# 02-WIFT_BT.net
KiCad netlist of a schematic drawn in Altium Designer
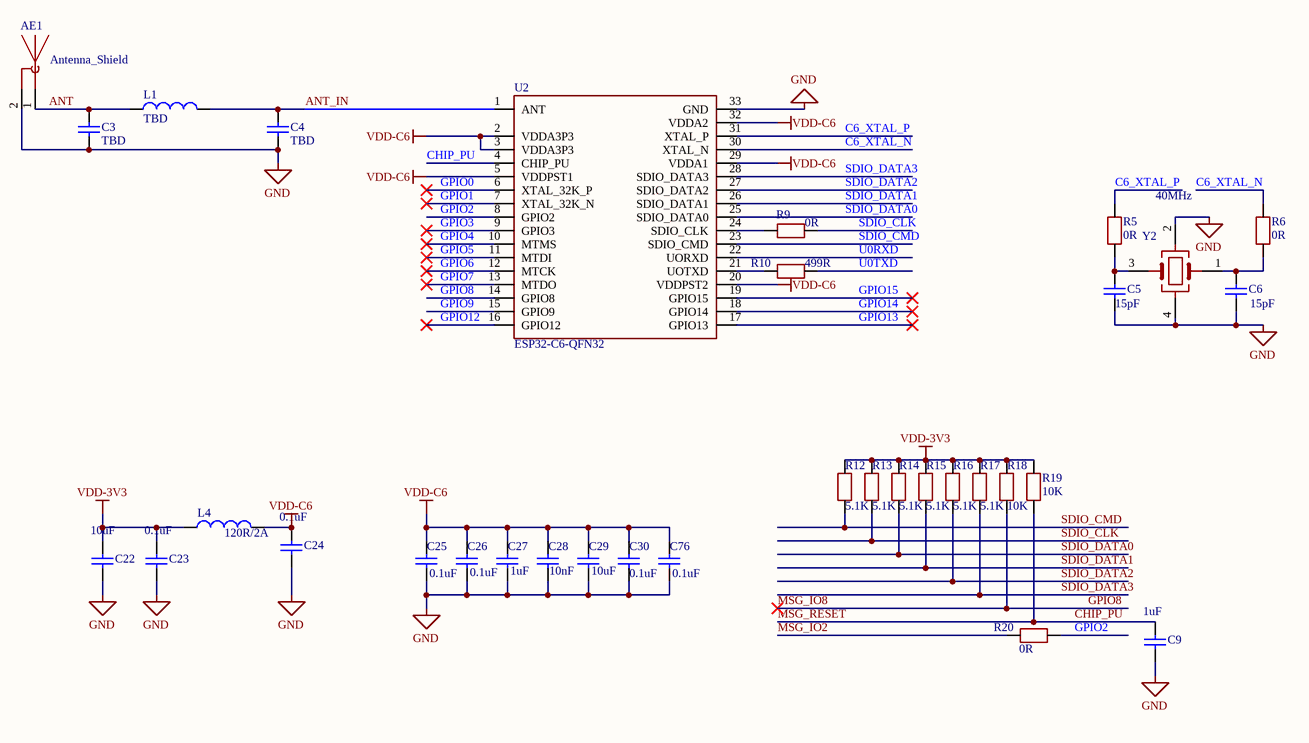
[diagram p0: 02-WIFT+BT.SchDoc]

(export (version "E")
  (design (tool "Eeschema 10.0.6"))
  (components
    (comp (ref "AE1")
      (value "Antenna_Shield")
      (footprint "ANT")
      (libsource (lib "222222") (part "Component_1"))
    )
    (comp (ref "C3")
      (value "TBD")
      (footprint "C0402")
      (description "Capacitor")
      (libsource (lib "Simulation Generic Components") (part "Capacitor"))
    )
    (comp (ref "C4")
      (value "TBD")
      (footprint "C0402")
      (description "Capacitor")
      (libsource (lib "Simulation Generic Components") (part "Capacitor"))
    )
    (comp (ref "C5")
      (value "15pF")
      (footprint "C0402")
      (description "Capacitor")
      (libsource (lib "Simulation Generic Components") (part "Capacitor"))
    )
    (comp (ref "C6")
      (value "15pF")
      (footprint "C0402")
      (description "Capacitor")
      (libsource (lib "Simulation Generic Components") (part "Capacitor"))
    )
    (comp (ref "C9")
      (value "1uF")
      (footprint "C0402")
      (description "Capacitor")
      (libsource (lib "Simulation Generic Components") (part "Capacitor"))
    )
    (comp (ref "C22")
      (value "10uF")
      (footprint "C0805")
      (description "Capacitor")
      (libsource (lib "Simulation Generic Components") (part "Capacitor"))
    )
    (comp (ref "C23")
      (value "0.1uF")
      (footprint "C0402")
      (description "Capacitor")
      (libsource (lib "Simulation Generic Components") (part "Capacitor"))
    )
    (comp (ref "C24")
      (value "0.1uF")
      (footprint "C0402")
      (description "Capacitor")
      (libsource (lib "Simulation Generic Components") (part "Capacitor"))
    )
    (comp (ref "C25")
      (value "0.1uF")
      (footprint "C0402")
      (description "Capacitor")
      (libsource (lib "Simulation Generic Components") (part "Capacitor"))
    )
    (comp (ref "C26")
      (value "0.1uF")
      (footprint "C0402")
      (description "Capacitor")
      (libsource (lib "Simulation Generic Components") (part "Capacitor"))
    )
    (comp (ref "C27")
      (value "1uF")
      (footprint "C0402")
      (description "Capacitor")
      (libsource (lib "Simulation Generic Components") (part "Capacitor"))
    )
    (comp (ref "C28")
      (value "10nF")
      (footprint "C0402")
      (description "Capacitor")
      (libsource (lib "Simulation Generic Components") (part "Capacitor"))
    )
    (comp (ref "C29")
      (value "10uF")
      (footprint "C0805")
      (description "Capacitor")
      (libsource (lib "Simulation Generic Components") (part "Capacitor"))
    )
    (comp (ref "C30")
      (value "0.1uF")
      (footprint "C0402")
      (description "Capacitor")
      (libsource (lib "Simulation Generic Components") (part "Capacitor"))
    )
    (comp (ref "C76")
      (value "0.1uF")
      (footprint "C0402")
      (description "Capacitor")
      (libsource (lib "Simulation Generic Components") (part "Capacitor"))
    )
    (comp (ref "L1")
      (value "TBD")
      (footprint "L0603")
      (description "Inductor")
      (libsource (lib "Simulation Generic Components") (part "Inductor"))
    )
    (comp (ref "L4")
      (value "120R/2A")
      (footprint "L0603")
      (description "Inductor")
      (libsource (lib "Simulation Generic Components") (part "Inductor"))
    )
    (comp (ref "R5") (value "0R") (footprint "R0402") (libsource (lib "PCB_Project") (part "R")))
    (comp (ref "R6") (value "0R") (footprint "R0402") (libsource (lib "PCB_Project") (part "R")))
    (comp (ref "R9") (value "0R") (footprint "R0402") (libsource (lib "PCB_Project") (part "R")))
    (comp (ref "R10") (value "499R") (footprint "R0402") (libsource (lib "PCB_Project") (part "R")))
    (comp (ref "R12") (value "5.1K") (footprint "R0402") (libsource (lib "PCB_Project") (part "R")))
    (comp (ref "R13") (value "5.1K") (footprint "R0402") (libsource (lib "PCB_Project") (part "R")))
    (comp (ref "R14") (value "5.1K") (footprint "R0402") (libsource (lib "PCB_Project") (part "R")))
    (comp (ref "R15") (value "5.1K") (footprint "R0402") (libsource (lib "PCB_Project") (part "R")))
    (comp (ref "R16") (value "5.1K") (footprint "R0402") (libsource (lib "PCB_Project") (part "R")))
    (comp (ref "R17") (value "5.1K") (footprint "R0402") (libsource (lib "PCB_Project") (part "R")))
    (comp (ref "R18") (value "10K") (footprint "R0402") (libsource (lib "PCB_Project") (part "R")))
    (comp (ref "R19") (value "10K") (footprint "R0402") (libsource (lib "PCB_Project") (part "R")))
    (comp (ref "R20") (value "0R") (footprint "R0402") (libsource (lib "PCB_Project") (part "R")))
    (comp (ref "U2")
      (value "ESP32-C6-QFN32")
      (footprint "QFN-32_L5.0-W5.0-P0.50-TL-EP3.7")
      (libsource (lib "222222") (part "ESP32-C6-QFN32"))
    )
    (comp (ref "Y2")
      (value "40MHz")
      (footprint "OSC-SMD_4P-L3.2-W2.5-BL_SIT8008BI")
      (libsource (lib "222222") (part "Component_3"))
    )
  )
  (nets
    (net (code "1") (name "/ANT") (class "Default")
      (node (ref "AE1") (pin "1") (pinfunction "1_1") (pintype "passive"))
      (node (ref "C3") (pin "2") (pinfunction "2_2") (pintype "passive"))
      (node (ref "L1") (pin "1") (pinfunction "1_1") (pintype "passive"))
    )
    (net (code "2") (name "/ANT_IN") (class "Default")
      (node (ref "C4") (pin "2") (pinfunction "2_2") (pintype "passive"))
      (node (ref "L1") (pin "2") (pinfunction "2_2") (pintype "passive"))
      (node (ref "U2") (pin "1") (pinfunction "ANT_1") (pintype "passive"))
    )
    (net (code "3") (name "/C6_XTAL_N") (class "Default")
      (node (ref "R6") (pin "2") (pinfunction "2_2") (pintype "passive"))
      (node (ref "U2") (pin "30") (pinfunction "XTAL_N_30") (pintype "passive"))
    )
    (net (code "4") (name "/C6_XTAL_P") (class "Default")
      (node (ref "R5") (pin "2") (pinfunction "2_2") (pintype "passive"))
      (node (ref "U2") (pin "31") (pinfunction "XTAL_P_31") (pintype "passive"))
    )
    (net (code "5") (name "/CHIP_PU") (class "Default")
      (node (ref "C9") (pin "2") (pinfunction "2_2") (pintype "passive"))
      (node (ref "R19") (pin "2") (pinfunction "2_2") (pintype "passive"))
      (node (ref "U2") (pin "4") (pinfunction "CHIP_PU_4") (pintype "passive"))
    )
    (net (code "6") (name "/GPIO0") (class "Default")
      (node (ref "U2") (pin "6") (pinfunction "XTAL_32K_P_6") (pintype "passive+no_connect"))
    )
    (net (code "7") (name "/GPIO1") (class "Default")
      (node (ref "U2") (pin "7") (pinfunction "XTAL_32K_N_7") (pintype "passive+no_connect"))
    )
    (net (code "8") (name "/GPIO2") (class "Default")
      (node (ref "R20") (pin "2") (pinfunction "2_2") (pintype "passive"))
      (node (ref "U2") (pin "8") (pinfunction "GPIO2_8") (pintype "passive"))
    )
    (net (code "9") (name "/GPIO3") (class "Default")
      (node (ref "U2") (pin "9") (pinfunction "GPIO3_9") (pintype "passive+no_connect"))
    )
    (net (code "10") (name "/GPIO4") (class "Default")
      (node (ref "U2") (pin "10") (pinfunction "MTMS_10") (pintype "passive+no_connect"))
    )
    (net (code "11") (name "/GPIO5") (class "Default")
      (node (ref "U2") (pin "11") (pinfunction "MTDI_11") (pintype "passive+no_connect"))
    )
    (net (code "12") (name "/GPIO6") (class "Default")
      (node (ref "U2") (pin "12") (pinfunction "MTCK_12") (pintype "passive+no_connect"))
    )
    (net (code "13") (name "/GPIO7") (class "Default")
      (node (ref "U2") (pin "13") (pinfunction "MTDO_13") (pintype "passive+no_connect"))
    )
    (net (code "14") (name "/GPIO8") (class "Default")
      (node (ref "R18") (pin "2") (pinfunction "2_2") (pintype "passive"))
      (node (ref "U2") (pin "14") (pinfunction "GPIO8_14") (pintype "passive"))
    )
    (net (code "15") (name "/GPIO9") (class "Default")
      (node (ref "U2") (pin "15") (pinfunction "GPIO9_15") (pintype "passive"))
    )
    (net (code "16") (name "/GPIO12") (class "Default")
      (node (ref "U2") (pin "16") (pinfunction "GPIO12_16") (pintype "passive+no_connect"))
    )
    (net (code "17") (name "/GPIO13") (class "Default")
      (node (ref "U2") (pin "17") (pinfunction "GPIO13_17") (pintype "passive+no_connect"))
    )
    (net (code "18") (name "/GPIO14") (class "Default")
      (node (ref "U2") (pin "18") (pinfunction "GPIO14_18") (pintype "passive+no_connect"))
    )
    (net (code "19") (name "/GPIO15") (class "Default")
      (node (ref "U2") (pin "19") (pinfunction "GPIO15_19") (pintype "passive+no_connect"))
    )
    (net (code "20") (name "/MSG_IO2") (class "Default")
      (node (ref "R20") (pin "1") (pinfunction "1_1") (pintype "passive"))
    )
    (net (code "21") (name "/SDIO_CLK") (class "Default")
      (node (ref "R13") (pin "2") (pinfunction "2_2") (pintype "passive"))
      (node (ref "R9") (pin "2") (pinfunction "2_2") (pintype "passive"))
    )
    (net (code "22") (name "/SDIO_CMD") (class "Default")
      (node (ref "R12") (pin "2") (pinfunction "2_2") (pintype "passive"))
      (node (ref "U2") (pin "23") (pinfunction "SDIO_CMD_23") (pintype "passive"))
    )
    (net (code "23") (name "/SDIO_DATA0") (class "Default")
      (node (ref "R14") (pin "2") (pinfunction "2_2") (pintype "passive"))
      (node (ref "U2") (pin "25") (pinfunction "SDIO_DATA0_25") (pintype "passive"))
    )
    (net (code "24") (name "/SDIO_DATA1") (class "Default")
      (node (ref "R15") (pin "2") (pinfunction "2_2") (pintype "passive"))
      (node (ref "U2") (pin "26") (pinfunction "SDIO_DATA1_26") (pintype "passive"))
    )
    (net (code "25") (name "/SDIO_DATA2") (class "Default")
      (node (ref "R16") (pin "2") (pinfunction "2_2") (pintype "passive"))
      (node (ref "U2") (pin "27") (pinfunction "SDIO_DATA2_27") (pintype "passive"))
    )
    (net (code "26") (name "/SDIO_DATA3") (class "Default")
      (node (ref "R17") (pin "2") (pinfunction "2_2") (pintype "passive"))
      (node (ref "U2") (pin "28") (pinfunction "SDIO_DATA3_28") (pintype "passive"))
    )
    (net (code "27") (name "/U0RXD") (class "Default")
      (node (ref "U2") (pin "22") (pinfunction "UORXD_22") (pintype "passive"))
    )
    (net (code "28") (name "/U0TXD") (class "Default")
      (node (ref "R10") (pin "2") (pinfunction "2_2") (pintype "passive"))
    )
    (net (code "29") (name "GND") (class "Default")
      (node (ref "AE1") (pin "2") (pinfunction "2_2") (pintype "passive"))
      (node (ref "C22") (pin "1") (pinfunction "1_1") (pintype "passive"))
      (node (ref "C23") (pin "1") (pinfunction "1_1") (pintype "passive"))
      (node (ref "C24") (pin "2") (pinfunction "2_2") (pintype "passive"))
      (node (ref "C25") (pin "2") (pinfunction "2_2") (pintype "passive"))
      (node (ref "C26") (pin "2") (pinfunction "2_2") (pintype "passive"))
      (node (ref "C27") (pin "2") (pinfunction "2_2") (pintype "passive"))
      (node (ref "C28") (pin "2") (pinfunction "2_2") (pintype "passive"))
      (node (ref "C29") (pin "2") (pinfunction "2_2") (pintype "passive"))
      (node (ref "C3") (pin "1") (pinfunction "1_1") (pintype "passive"))
      (node (ref "C30") (pin "1") (pinfunction "1_1") (pintype "passive"))
      (node (ref "C4") (pin "1") (pinfunction "1_1") (pintype "passive"))
      (node (ref "C5") (pin "2") (pinfunction "2_2") (pintype "passive"))
      (node (ref "C6") (pin "2") (pinfunction "2_2") (pintype "passive"))
      (node (ref "C76") (pin "2") (pinfunction "2_2") (pintype "passive"))
      (node (ref "C9") (pin "1") (pinfunction "1_1") (pintype "passive"))
      (node (ref "U2") (pin "33") (pinfunction "GND_33") (pintype "passive"))
      (node (ref "Y2") (pin "2") (pinfunction "2_2") (pintype "passive"))
      (node (ref "Y2") (pin "4") (pinfunction "4_4") (pintype "passive"))
    )
    (net (code "30") (name "Net-(C5-Pad1)") (class "Default")
      (node (ref "C5") (pin "1") (pinfunction "1_1") (pintype "passive"))
      (node (ref "R5") (pin "1") (pinfunction "1_1") (pintype "passive"))
      (node (ref "Y2") (pin "3") (pinfunction "3_3") (pintype "passive"))
    )
    (net (code "31") (name "Net-(C6-Pad1)") (class "Default")
      (node (ref "C6") (pin "1") (pinfunction "1_1") (pintype "passive"))
      (node (ref "R6") (pin "1") (pinfunction "1_1") (pintype "passive"))
      (node (ref "Y2") (pin "1") (pinfunction "1_1") (pintype "passive"))
    )
    (net (code "32") (name "Net-(U2-SDIO_CLK)") (class "Default")
      (node (ref "R9") (pin "1") (pinfunction "1_1") (pintype "passive"))
      (node (ref "U2") (pin "24") (pinfunction "SDIO_CLK_24") (pintype "passive"))
    )
    (net (code "33") (name "Net-(U2-UOTXD)") (class "Default")
      (node (ref "R10") (pin "1") (pinfunction "1_1") (pintype "passive"))
      (node (ref "U2") (pin "21") (pinfunction "UOTXD_21") (pintype "passive"))
    )
    (net (code "34") (name "VDD-3V3") (class "Default")
      (node (ref "C22") (pin "2") (pinfunction "2_2") (pintype "passive"))
      (node (ref "C23") (pin "2") (pinfunction "2_2") (pintype "passive"))
      (node (ref "L4") (pin "1") (pinfunction "1_1") (pintype "passive"))
      (node (ref "R12") (pin "1") (pinfunction "1_1") (pintype "passive"))
      (node (ref "R13") (pin "1") (pinfunction "1_1") (pintype "passive"))
      (node (ref "R14") (pin "1") (pinfunction "1_1") (pintype "passive"))
      (node (ref "R15") (pin "1") (pinfunction "1_1") (pintype "passive"))
      (node (ref "R16") (pin "1") (pinfunction "1_1") (pintype "passive"))
      (node (ref "R17") (pin "1") (pinfunction "1_1") (pintype "passive"))
      (node (ref "R18") (pin "1") (pinfunction "1_1") (pintype "passive"))
      (node (ref "R19") (pin "1") (pinfunction "1_1") (pintype "passive"))
    )
    (net (code "35") (name "VDD-C6") (class "Default")
      (node (ref "C24") (pin "1") (pinfunction "1_1") (pintype "passive"))
      (node (ref "C25") (pin "1") (pinfunction "1_1") (pintype "passive"))
      (node (ref "C26") (pin "1") (pinfunction "1_1") (pintype "passive"))
      (node (ref "C27") (pin "1") (pinfunction "1_1") (pintype "passive"))
      (node (ref "C28") (pin "1") (pinfunction "1_1") (pintype "passive"))
      (node (ref "C29") (pin "1") (pinfunction "1_1") (pintype "passive"))
      (node (ref "C30") (pin "2") (pinfunction "2_2") (pintype "passive"))
      (node (ref "C76") (pin "1") (pinfunction "1_1") (pintype "passive"))
      (node (ref "L4") (pin "2") (pinfunction "2_2") (pintype "passive"))
      (node (ref "U2") (pin "2") (pinfunction "VDDA3P3_2") (pintype "passive"))
      (node (ref "U2") (pin "20") (pinfunction "VDDPST2_20") (pintype "passive"))
      (node (ref "U2") (pin "29") (pinfunction "VDDA1_29") (pintype "passive"))
      (node (ref "U2") (pin "3") (pinfunction "VDDA3P3_3") (pintype "passive"))
      (node (ref "U2") (pin "32") (pinfunction "VDDA2_32") (pintype "passive"))
      (node (ref "U2") (pin "5") (pinfunction "VDDPST1_5") (pintype "passive"))
    )
  )
)
